# Power_Sandwitch.net
KiCad netlist of a schematic drawn in EAGLE
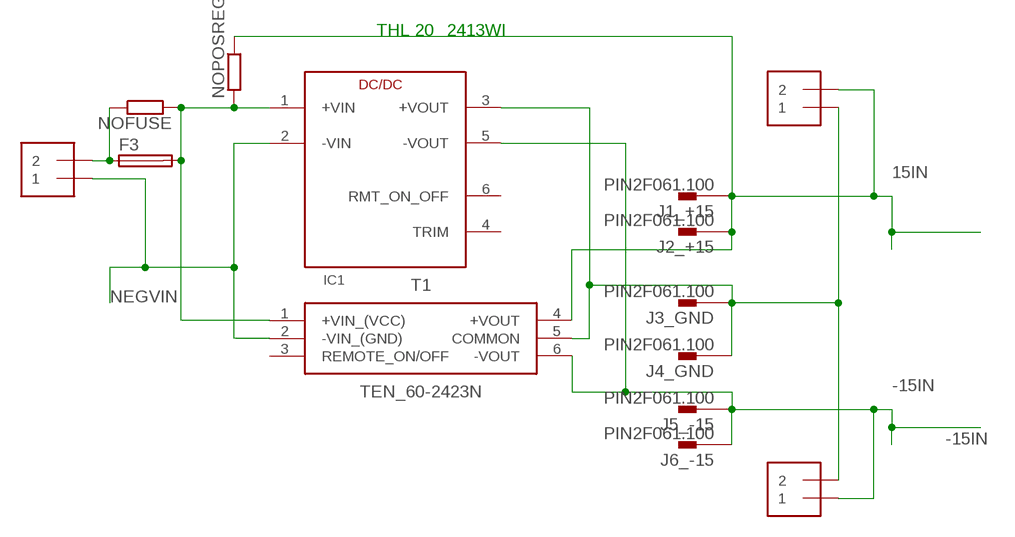
[diagram p0: schematic, sheet 1]

(export (version "E")
  (design (tool "Eeschema 10.0.6"))
  (components
    (comp (ref "DC_IN")
      (value "1X2-3.5MM")
      (footprint "eagle-import:1X2-3.5MM")
      (libsource (lib "eagle-import") (part "1X2-3.5MM"))
    )
    (comp (ref "DC_IN1")
      (value "1X2-3.5MM")
      (footprint "eagle-import:1X2-3.5MM")
      (libsource (lib "eagle-import") (part "1X2-3.5MM"))
    )
    (comp (ref "DC_IN2")
      (value "1X2-3.5MM")
      (footprint "eagle-import:1X2-3.5MM")
      (libsource (lib "eagle-import") (part "1X2-3.5MM"))
    )
    (comp (ref "F3")
      (value "GSH15")
      (footprint "eagle-import:GSH15")
      (fields (field (name "MPN") "64900001039"))
      (libsource (lib "eagle-import") (part "GSH15"))
    )
    (comp (ref "IC1")
      (value "THL_20WI_SERIES")
      (footprint "eagle-import:THL_20WI_SERIES")
      (libsource (lib "eagle-import") (part "THL_20WI_SERIES"))
    )
    (comp (ref "J1_+15")
      (value "PIN2F061.100")
      (footprint "eagle-import:F061.100")
      (libsource (lib "eagle-import") (part "PIN2F061.100"))
    )
    (comp (ref "J2_+15")
      (value "PIN2F061.100")
      (footprint "eagle-import:F061.100")
      (libsource (lib "eagle-import") (part "PIN2F061.100"))
    )
    (comp (ref "J3_GND")
      (value "PIN2F061.100")
      (footprint "eagle-import:F061.100")
      (libsource (lib "eagle-import") (part "PIN2F061.100"))
    )
    (comp (ref "J4_GND")
      (value "PIN2F061.100")
      (footprint "eagle-import:F061.100")
      (libsource (lib "eagle-import") (part "PIN2F061.100"))
    )
    (comp (ref "J5_-15")
      (value "PIN2F061.100")
      (footprint "eagle-import:F061.100")
      (libsource (lib "eagle-import") (part "PIN2F061.100"))
    )
    (comp (ref "J6_-15")
      (value "PIN2F061.100")
      (footprint "eagle-import:F061.100")
      (libsource (lib "eagle-import") (part "PIN2F061.100"))
    )
    (comp (ref "NOFUSE")
      (value "SMT-REF")
      (footprint "eagle-import:SMT-REF")
      (libsource (lib "eagle-import") (part "SMT-REF"))
    )
    (comp (ref "NOPOSREG")
      (value "SMT-REF")
      (footprint "eagle-import:SMT-REF")
      (libsource (lib "eagle-import") (part "SMT-REF"))
    )
    (comp (ref "T1")
      (value "TEN_60-2423N")
      (footprint "eagle-import:TEN60-2423N")
      (fields
        (field (name "MANUFACTURER_PART_NUMBER") "TEN 60-2423N")
        (field (name "RS_PART_NUMBER") "7882705")
      )
      (libsource (lib "eagle-import") (part "TEN_60-2423N"))
    )
  )
  (nets
    (net (code "1") (name "/-15IN") (class "Default")
      (node (ref "DC_IN2") (pin "1") (pinfunction "1_1") (pintype "passive"))
      (node (ref "IC1") (pin "5") (pinfunction "-VOUT_5") (pintype "passive"))
      (node (ref "J5_-15") (pin "A1") (pinfunction "1_A1") (pintype "passive"))
      (node (ref "J5_-15") (pin "A2") (pinfunction "1_A2") (pintype "passive"))
      (node (ref "J6_-15") (pin "A1") (pinfunction "1_A1") (pintype "passive"))
      (node (ref "J6_-15") (pin "A2") (pinfunction "1_A2") (pintype "passive"))
      (node (ref "T1") (pin "6") (pinfunction "-VOUT_6") (pintype "passive"))
    )
    (net (code "2") (name "/15IN") (class "Default")
      (node (ref "DC_IN1") (pin "2") (pinfunction "2_2") (pintype "passive"))
      (node (ref "J1_+15") (pin "A1") (pinfunction "1_A1") (pintype "passive"))
      (node (ref "J1_+15") (pin "A2") (pinfunction "1_A2") (pintype "passive"))
      (node (ref "J2_+15") (pin "A1") (pinfunction "1_A1") (pintype "passive"))
      (node (ref "J2_+15") (pin "A2") (pinfunction "1_A2") (pintype "passive"))
      (node (ref "NOPOSREG") (pin "1") (pinfunction "1_1") (pintype "passive"))
      (node (ref "T1") (pin "4") (pinfunction "+VOUT_4") (pintype "passive"))
    )
    (net (code "3") (name "/NEGVIN") (class "Default")
      (node (ref "DC_IN") (pin "1") (pinfunction "1_1") (pintype "passive"))
      (node (ref "IC1") (pin "2") (pinfunction "-VIN_2") (pintype "input"))
      (node (ref "T1") (pin "2") (pinfunction "-VIN_(GND)_2") (pintype "passive"))
    )
    (net (code "4") (name "Net-(DC_IN-Pad2)") (class "Default")
      (node (ref "DC_IN") (pin "2") (pinfunction "2_2") (pintype "passive"))
      (node (ref "F3") (pin "1") (pinfunction "1_1") (pintype "passive"))
      (node (ref "NOFUSE") (pin "1") (pinfunction "1_1") (pintype "passive"))
    )
    (net (code "5") (name "Net-(IC1-+VIN)") (class "Default")
      (node (ref "F3") (pin "2") (pinfunction "2_2") (pintype "passive"))
      (node (ref "IC1") (pin "1") (pinfunction "+VIN_1") (pintype "input"))
      (node (ref "NOFUSE") (pin "2") (pinfunction "2_2") (pintype "passive"))
      (node (ref "NOPOSREG") (pin "2") (pinfunction "2_2") (pintype "passive"))
      (node (ref "T1") (pin "1") (pinfunction "+VIN_(VCC)_1") (pintype "passive"))
    )
    (net (code "6") (name "Net-(IC1-+VOUT)") (class "Default")
      (node (ref "DC_IN1") (pin "1") (pinfunction "1_1") (pintype "passive"))
      (node (ref "DC_IN2") (pin "2") (pinfunction "2_2") (pintype "passive"))
      (node (ref "IC1") (pin "3") (pinfunction "+VOUT_3") (pintype "passive"))
      (node (ref "J3_GND") (pin "A1") (pinfunction "1_A1") (pintype "passive"))
      (node (ref "J3_GND") (pin "A2") (pinfunction "1_A2") (pintype "passive"))
      (node (ref "J4_GND") (pin "A1") (pinfunction "1_A1") (pintype "passive"))
      (node (ref "J4_GND") (pin "A2") (pinfunction "1_A2") (pintype "passive"))
      (node (ref "T1") (pin "5") (pinfunction "COMMON_5") (pintype "passive"))
    )
    (net (code "7") (name "unconnected-(IC1-RMT_ON_OFF-Pad6)") (class "Default")
      (node (ref "IC1") (pin "6") (pinfunction "RMT_ON_OFF_6") (pintype "input"))
    )
    (net (code "8") (name "unconnected-(IC1-TRIM-Pad4)") (class "Default")
      (node (ref "IC1") (pin "4") (pinfunction "TRIM_4") (pintype "input"))
    )
    (net (code "9") (name "unconnected-(T1-REMOTE_ON{slash}OFF-Pad3)") (class "Default")
      (node (ref "T1") (pin "3") (pinfunction "REMOTE_ON/OFF_3") (pintype "passive"))
    )
  )
)
